# Sheet3.net
KiCad netlist of a schematic drawn in Altium Designer
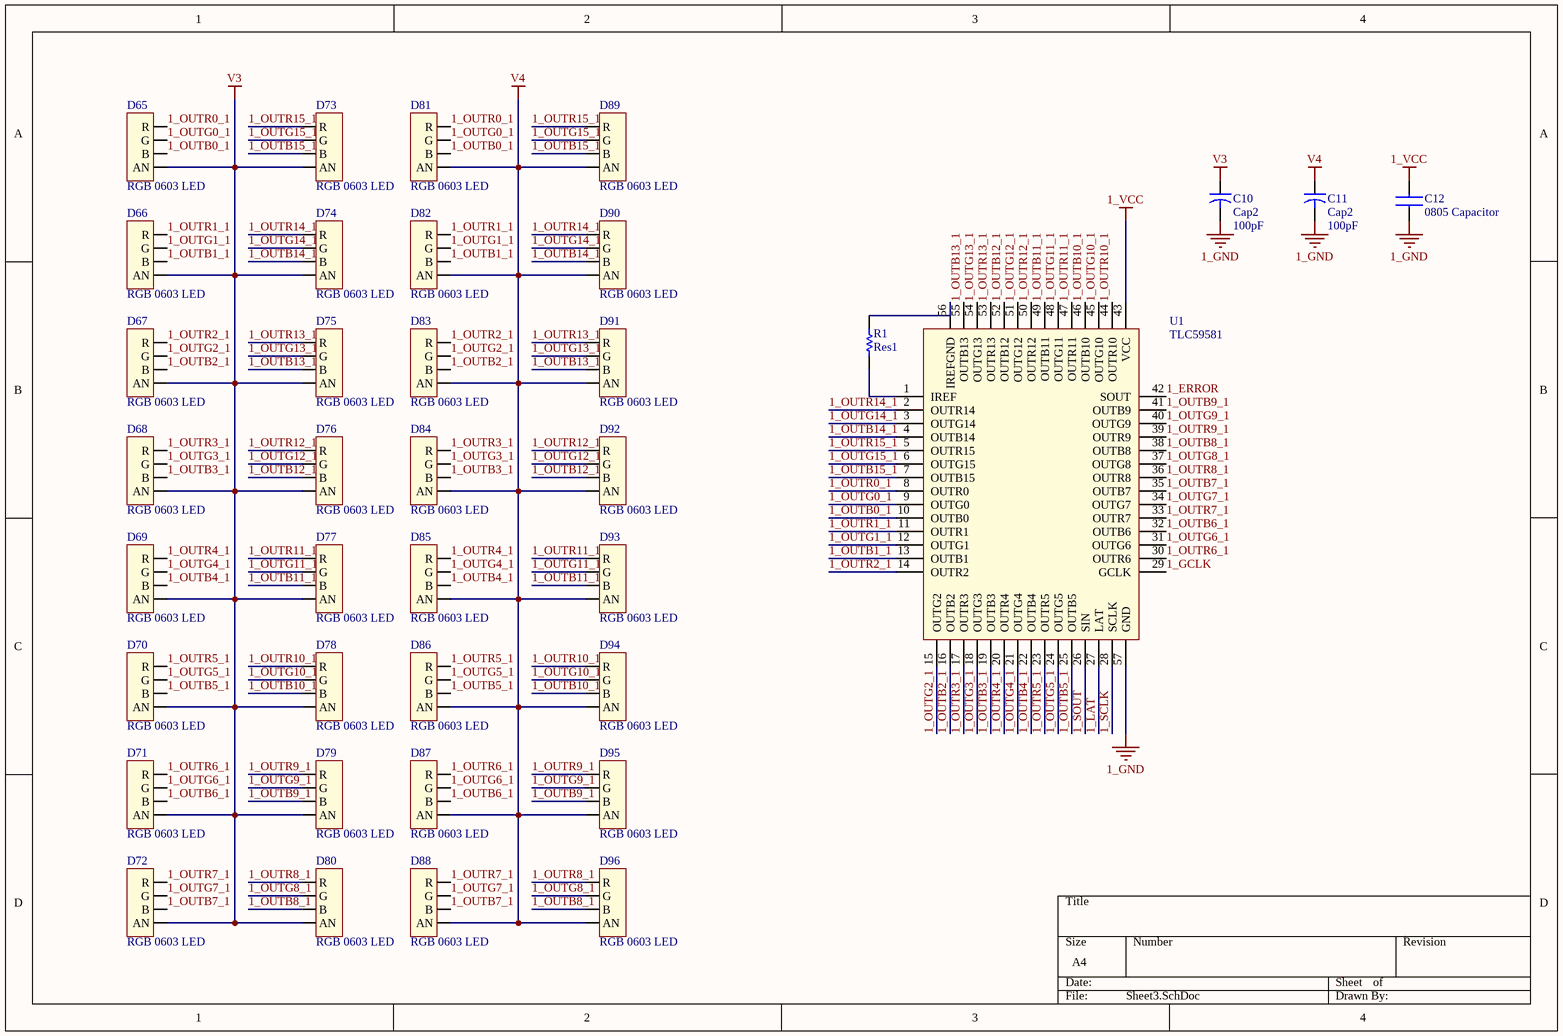
[diagram p0: Sheet3.SchDoc]

(export (version "E")
  (design (tool "Eeschema 10.0.6"))
  (components
    (comp (ref "C10")
      (value "Cap2")
      (footprint "CAPR5-4X5")
      (description "Capacitor")
      (fields (field (name "ALTIUM_VALUE") "100pF") (field (name "PUBLISHER") "Altium Limited"))
      (libsource (lib "Miscellaneous Devices") (part "Cap2"))
    )
    (comp (ref "C11")
      (value "Cap2")
      (footprint "CAPR5-4X5")
      (description "Capacitor")
      (fields (field (name "ALTIUM_VALUE") "100pF") (field (name "PUBLISHER") "Altium Limited"))
      (libsource (lib "Miscellaneous Devices") (part "Cap2"))
    )
    (comp (ref "C12")
      (value "0805 Capacitor")
      (footprint "0805 Capacitor")
      (libsource (lib "Schlib1") (part "0805 Capacitor"))
    )
    (comp (ref "D65")
      (value "RGB 0603 LED")
      (footprint "RGB LED")
      (libsource (lib "") (part "RGB 0603 LED_1"))
    )
    (comp (ref "D66")
      (value "RGB 0603 LED")
      (footprint "RGB LED")
      (libsource (lib "") (part "RGB 0603 LED_1"))
    )
    (comp (ref "D67")
      (value "RGB 0603 LED")
      (footprint "RGB LED")
      (libsource (lib "") (part "RGB 0603 LED_1"))
    )
    (comp (ref "D68")
      (value "RGB 0603 LED")
      (footprint "RGB LED")
      (libsource (lib "") (part "RGB 0603 LED_1"))
    )
    (comp (ref "D69")
      (value "RGB 0603 LED")
      (footprint "RGB LED")
      (libsource (lib "") (part "RGB 0603 LED_1"))
    )
    (comp (ref "D70")
      (value "RGB 0603 LED")
      (footprint "RGB LED")
      (libsource (lib "") (part "RGB 0603 LED_1"))
    )
    (comp (ref "D71")
      (value "RGB 0603 LED")
      (footprint "RGB LED")
      (libsource (lib "") (part "RGB 0603 LED_1"))
    )
    (comp (ref "D72")
      (value "RGB 0603 LED")
      (footprint "RGB LED")
      (libsource (lib "") (part "RGB 0603 LED_1"))
    )
    (comp (ref "D73")
      (value "RGB 0603 LED")
      (footprint "RGB LED")
      (libsource (lib "Schlib1") (part "RGB 0603 LED"))
    )
    (comp (ref "D74")
      (value "RGB 0603 LED")
      (footprint "RGB LED")
      (libsource (lib "Schlib1") (part "RGB 0603 LED"))
    )
    (comp (ref "D75")
      (value "RGB 0603 LED")
      (footprint "RGB LED")
      (libsource (lib "Schlib1") (part "RGB 0603 LED"))
    )
    (comp (ref "D76")
      (value "RGB 0603 LED")
      (footprint "RGB LED")
      (libsource (lib "Schlib1") (part "RGB 0603 LED"))
    )
    (comp (ref "D77")
      (value "RGB 0603 LED")
      (footprint "RGB LED")
      (libsource (lib "Schlib1") (part "RGB 0603 LED"))
    )
    (comp (ref "D78")
      (value "RGB 0603 LED")
      (footprint "RGB LED")
      (libsource (lib "Schlib1") (part "RGB 0603 LED"))
    )
    (comp (ref "D79")
      (value "RGB 0603 LED")
      (footprint "RGB LED")
      (libsource (lib "Schlib1") (part "RGB 0603 LED"))
    )
    (comp (ref "D80")
      (value "RGB 0603 LED")
      (footprint "RGB LED")
      (libsource (lib "Schlib1") (part "RGB 0603 LED"))
    )
    (comp (ref "D81")
      (value "RGB 0603 LED")
      (footprint "RGB LED")
      (libsource (lib "") (part "RGB 0603 LED_1"))
    )
    (comp (ref "D82")
      (value "RGB 0603 LED")
      (footprint "RGB LED")
      (libsource (lib "") (part "RGB 0603 LED_1"))
    )
    (comp (ref "D83")
      (value "RGB 0603 LED")
      (footprint "RGB LED")
      (libsource (lib "") (part "RGB 0603 LED_1"))
    )
    (comp (ref "D84")
      (value "RGB 0603 LED")
      (footprint "RGB LED")
      (libsource (lib "") (part "RGB 0603 LED_1"))
    )
    (comp (ref "D85")
      (value "RGB 0603 LED")
      (footprint "RGB LED")
      (libsource (lib "") (part "RGB 0603 LED_1"))
    )
    (comp (ref "D86")
      (value "RGB 0603 LED")
      (footprint "RGB LED")
      (libsource (lib "") (part "RGB 0603 LED_1"))
    )
    (comp (ref "D87")
      (value "RGB 0603 LED")
      (footprint "RGB LED")
      (libsource (lib "") (part "RGB 0603 LED_1"))
    )
    (comp (ref "D88")
      (value "RGB 0603 LED")
      (footprint "RGB LED")
      (libsource (lib "") (part "RGB 0603 LED_1"))
    )
    (comp (ref "D89")
      (value "RGB 0603 LED")
      (footprint "RGB LED")
      (libsource (lib "Schlib1") (part "RGB 0603 LED"))
    )
    (comp (ref "D90")
      (value "RGB 0603 LED")
      (footprint "RGB LED")
      (libsource (lib "Schlib1") (part "RGB 0603 LED"))
    )
    (comp (ref "D91")
      (value "RGB 0603 LED")
      (footprint "RGB LED")
      (libsource (lib "Schlib1") (part "RGB 0603 LED"))
    )
    (comp (ref "D92")
      (value "RGB 0603 LED")
      (footprint "RGB LED")
      (libsource (lib "Schlib1") (part "RGB 0603 LED"))
    )
    (comp (ref "D93")
      (value "RGB 0603 LED")
      (footprint "RGB LED")
      (libsource (lib "Schlib1") (part "RGB 0603 LED"))
    )
    (comp (ref "D94")
      (value "RGB 0603 LED")
      (footprint "RGB LED")
      (libsource (lib "Schlib1") (part "RGB 0603 LED"))
    )
    (comp (ref "D95")
      (value "RGB 0603 LED")
      (footprint "RGB LED")
      (libsource (lib "Schlib1") (part "RGB 0603 LED"))
    )
    (comp (ref "D96")
      (value "RGB 0603 LED")
      (footprint "RGB LED")
      (libsource (lib "Schlib1") (part "RGB 0603 LED"))
    )
    (comp (ref "R1")
      (value "Res1")
      (footprint "AXIAL-0.3")
      (description "Resistor")
      (fields (field (name "PUBLISHER") "Altium Limited"))
      (libsource (lib "Miscellaneous Devices") (part "Res1"))
    )
    (comp (ref "U1") (value "TLC59581") (footprint "TLC59581") (libsource (lib "Schlib1") (part "TLC59581")))
  )
  (nets
    (net (code "1") (name "/1_ERROR") (class "Default")
      (node (ref "U1") (pin "42") (pinfunction "SOUT_42") (pintype "passive"))
    )
    (net (code "2") (name "/1_GCLK") (class "Default")
      (node (ref "U1") (pin "29") (pinfunction "GCLK_29") (pintype "passive"))
    )
    (net (code "3") (name "/1_LAT") (class "Default")
      (node (ref "U1") (pin "27") (pinfunction "LAT_27") (pintype "passive"))
    )
    (net (code "4") (name "/1_OUTB0_1") (class "Default")
      (node (ref "D65") (pin "3") (pinfunction "B_3") (pintype "passive"))
      (node (ref "D81") (pin "3") (pinfunction "B_3") (pintype "passive"))
      (node (ref "U1") (pin "10") (pinfunction "OUTB0_10") (pintype "passive"))
    )
    (net (code "5") (name "/1_OUTB1_1") (class "Default")
      (node (ref "D66") (pin "3") (pinfunction "B_3") (pintype "passive"))
      (node (ref "D82") (pin "3") (pinfunction "B_3") (pintype "passive"))
      (node (ref "U1") (pin "13") (pinfunction "OUTB1_13") (pintype "passive"))
    )
    (net (code "6") (name "/1_OUTB2_1") (class "Default")
      (node (ref "D67") (pin "3") (pinfunction "B_3") (pintype "passive"))
      (node (ref "D83") (pin "3") (pinfunction "B_3") (pintype "passive"))
      (node (ref "U1") (pin "16") (pinfunction "OUTB2_16") (pintype "passive"))
    )
    (net (code "7") (name "/1_OUTB3_1") (class "Default")
      (node (ref "D68") (pin "3") (pinfunction "B_3") (pintype "passive"))
      (node (ref "D84") (pin "3") (pinfunction "B_3") (pintype "passive"))
      (node (ref "U1") (pin "19") (pinfunction "OUTB3_19") (pintype "passive"))
    )
    (net (code "8") (name "/1_OUTB4_1") (class "Default")
      (node (ref "D69") (pin "3") (pinfunction "B_3") (pintype "passive"))
      (node (ref "D85") (pin "3") (pinfunction "B_3") (pintype "passive"))
      (node (ref "U1") (pin "22") (pinfunction "OUTB4_22") (pintype "passive"))
    )
    (net (code "9") (name "/1_OUTB5_1") (class "Default")
      (node (ref "D70") (pin "3") (pinfunction "B_3") (pintype "passive"))
      (node (ref "D86") (pin "3") (pinfunction "B_3") (pintype "passive"))
      (node (ref "U1") (pin "25") (pinfunction "OUTB5_25") (pintype "passive"))
    )
    (net (code "10") (name "/1_OUTB6_1") (class "Default")
      (node (ref "D71") (pin "3") (pinfunction "B_3") (pintype "passive"))
      (node (ref "D87") (pin "3") (pinfunction "B_3") (pintype "passive"))
      (node (ref "U1") (pin "32") (pinfunction "OUTB6_32") (pintype "passive"))
    )
    (net (code "11") (name "/1_OUTB7_1") (class "Default")
      (node (ref "D72") (pin "3") (pinfunction "B_3") (pintype "passive"))
      (node (ref "D88") (pin "3") (pinfunction "B_3") (pintype "passive"))
      (node (ref "U1") (pin "35") (pinfunction "OUTB7_35") (pintype "passive"))
    )
    (net (code "12") (name "/1_OUTB8_1") (class "Default")
      (node (ref "D80") (pin "3") (pinfunction "B_3") (pintype "passive"))
      (node (ref "D96") (pin "3") (pinfunction "B_3") (pintype "passive"))
      (node (ref "U1") (pin "38") (pinfunction "OUTB8_38") (pintype "passive"))
    )
    (net (code "13") (name "/1_OUTB9_1") (class "Default")
      (node (ref "D79") (pin "3") (pinfunction "B_3") (pintype "passive"))
      (node (ref "D95") (pin "3") (pinfunction "B_3") (pintype "passive"))
      (node (ref "U1") (pin "41") (pinfunction "OUTB9_41") (pintype "passive"))
    )
    (net (code "14") (name "/1_OUTB10_1") (class "Default")
      (node (ref "D78") (pin "3") (pinfunction "B_3") (pintype "passive"))
      (node (ref "D94") (pin "3") (pinfunction "B_3") (pintype "passive"))
      (node (ref "U1") (pin "46") (pinfunction "OUTB10_46") (pintype "passive"))
    )
    (net (code "15") (name "/1_OUTB11_1") (class "Default")
      (node (ref "D77") (pin "3") (pinfunction "B_3") (pintype "passive"))
      (node (ref "D93") (pin "3") (pinfunction "B_3") (pintype "passive"))
      (node (ref "U1") (pin "49") (pinfunction "OUTB11_49") (pintype "passive"))
    )
    (net (code "16") (name "/1_OUTB12_1") (class "Default")
      (node (ref "D76") (pin "3") (pinfunction "B_3") (pintype "passive"))
      (node (ref "D92") (pin "3") (pinfunction "B_3") (pintype "passive"))
      (node (ref "U1") (pin "52") (pinfunction "OUTB12_52") (pintype "passive"))
    )
    (net (code "17") (name "/1_OUTB13_1") (class "Default")
      (node (ref "D75") (pin "3") (pinfunction "B_3") (pintype "passive"))
      (node (ref "D91") (pin "3") (pinfunction "B_3") (pintype "passive"))
      (node (ref "U1") (pin "55") (pinfunction "OUTB13_55") (pintype "passive"))
    )
    (net (code "18") (name "/1_OUTB14_1") (class "Default")
      (node (ref "D74") (pin "3") (pinfunction "B_3") (pintype "passive"))
      (node (ref "D90") (pin "3") (pinfunction "B_3") (pintype "passive"))
      (node (ref "U1") (pin "4") (pinfunction "OUTB14_4") (pintype "passive"))
    )
    (net (code "19") (name "/1_OUTB15_1") (class "Default")
      (node (ref "D73") (pin "3") (pinfunction "B_3") (pintype "passive"))
      (node (ref "D89") (pin "3") (pinfunction "B_3") (pintype "passive"))
      (node (ref "U1") (pin "7") (pinfunction "OUTB15_7") (pintype "passive"))
    )
    (net (code "20") (name "/1_OUTG0_1") (class "Default")
      (node (ref "D65") (pin "2") (pinfunction "G_2") (pintype "passive"))
      (node (ref "D81") (pin "2") (pinfunction "G_2") (pintype "passive"))
      (node (ref "U1") (pin "9") (pinfunction "OUTG0_9") (pintype "passive"))
    )
    (net (code "21") (name "/1_OUTG1_1") (class "Default")
      (node (ref "D66") (pin "2") (pinfunction "G_2") (pintype "passive"))
      (node (ref "D82") (pin "2") (pinfunction "G_2") (pintype "passive"))
      (node (ref "U1") (pin "12") (pinfunction "OUTG1_12") (pintype "passive"))
    )
    (net (code "22") (name "/1_OUTG2_1") (class "Default")
      (node (ref "D67") (pin "2") (pinfunction "G_2") (pintype "passive"))
      (node (ref "D83") (pin "2") (pinfunction "G_2") (pintype "passive"))
      (node (ref "U1") (pin "15") (pinfunction "OUTG2_15") (pintype "passive"))
    )
    (net (code "23") (name "/1_OUTG3_1") (class "Default")
      (node (ref "D68") (pin "2") (pinfunction "G_2") (pintype "passive"))
      (node (ref "D84") (pin "2") (pinfunction "G_2") (pintype "passive"))
      (node (ref "U1") (pin "18") (pinfunction "OUTG3_18") (pintype "passive"))
    )
    (net (code "24") (name "/1_OUTG4_1") (class "Default")
      (node (ref "D69") (pin "2") (pinfunction "G_2") (pintype "passive"))
      (node (ref "D85") (pin "2") (pinfunction "G_2") (pintype "passive"))
      (node (ref "U1") (pin "21") (pinfunction "OUTG4_21") (pintype "passive"))
    )
    (net (code "25") (name "/1_OUTG5_1") (class "Default")
      (node (ref "D70") (pin "2") (pinfunction "G_2") (pintype "passive"))
      (node (ref "D86") (pin "2") (pinfunction "G_2") (pintype "passive"))
      (node (ref "U1") (pin "24") (pinfunction "OUTG5_24") (pintype "passive"))
    )
    (net (code "26") (name "/1_OUTG6_1") (class "Default")
      (node (ref "D71") (pin "2") (pinfunction "G_2") (pintype "passive"))
      (node (ref "D87") (pin "2") (pinfunction "G_2") (pintype "passive"))
      (node (ref "U1") (pin "31") (pinfunction "OUTG6_31") (pintype "passive"))
    )
    (net (code "27") (name "/1_OUTG7_1") (class "Default")
      (node (ref "D72") (pin "2") (pinfunction "G_2") (pintype "passive"))
      (node (ref "D88") (pin "2") (pinfunction "G_2") (pintype "passive"))
      (node (ref "U1") (pin "34") (pinfunction "OUTG7_34") (pintype "passive"))
    )
    (net (code "28") (name "/1_OUTG8_1") (class "Default")
      (node (ref "D80") (pin "2") (pinfunction "G_2") (pintype "passive"))
      (node (ref "D96") (pin "2") (pinfunction "G_2") (pintype "passive"))
      (node (ref "U1") (pin "37") (pinfunction "OUTG8_37") (pintype "passive"))
    )
    (net (code "29") (name "/1_OUTG9_1") (class "Default")
      (node (ref "D79") (pin "2") (pinfunction "G_2") (pintype "passive"))
      (node (ref "D95") (pin "2") (pinfunction "G_2") (pintype "passive"))
      (node (ref "U1") (pin "40") (pinfunction "OUTG9_40") (pintype "passive"))
    )
    (net (code "30") (name "/1_OUTG10_1") (class "Default")
      (node (ref "D78") (pin "2") (pinfunction "G_2") (pintype "passive"))
      (node (ref "D94") (pin "2") (pinfunction "G_2") (pintype "passive"))
      (node (ref "U1") (pin "45") (pinfunction "OUTG10_45") (pintype "passive"))
    )
    (net (code "31") (name "/1_OUTG11_1") (class "Default")
      (node (ref "D77") (pin "2") (pinfunction "G_2") (pintype "passive"))
      (node (ref "D93") (pin "2") (pinfunction "G_2") (pintype "passive"))
      (node (ref "U1") (pin "48") (pinfunction "OUTG11_48") (pintype "passive"))
    )
    (net (code "32") (name "/1_OUTG12_1") (class "Default")
      (node (ref "D76") (pin "2") (pinfunction "G_2") (pintype "passive"))
      (node (ref "D92") (pin "2") (pinfunction "G_2") (pintype "passive"))
      (node (ref "U1") (pin "51") (pinfunction "OUTG12_51") (pintype "passive"))
    )
    (net (code "33") (name "/1_OUTG13_1") (class "Default")
      (node (ref "D75") (pin "2") (pinfunction "G_2") (pintype "passive"))
      (node (ref "D91") (pin "2") (pinfunction "G_2") (pintype "passive"))
      (node (ref "U1") (pin "54") (pinfunction "OUTG13_54") (pintype "passive"))
    )
    (net (code "34") (name "/1_OUTG14_1") (class "Default")
      (node (ref "D74") (pin "2") (pinfunction "G_2") (pintype "passive"))
      (node (ref "D90") (pin "2") (pinfunction "G_2") (pintype "passive"))
      (node (ref "U1") (pin "3") (pinfunction "OUTG14_3") (pintype "passive"))
    )
    (net (code "35") (name "/1_OUTG15_1") (class "Default")
      (node (ref "D73") (pin "2") (pinfunction "G_2") (pintype "passive"))
      (node (ref "D89") (pin "2") (pinfunction "G_2") (pintype "passive"))
      (node (ref "U1") (pin "6") (pinfunction "OUTG15_6") (pintype "passive"))
    )
    (net (code "36") (name "/1_OUTR0_1") (class "Default")
      (node (ref "D65") (pin "1") (pinfunction "R_1") (pintype "passive"))
      (node (ref "D81") (pin "1") (pinfunction "R_1") (pintype "passive"))
      (node (ref "U1") (pin "8") (pinfunction "OUTR0_8") (pintype "passive"))
    )
    (net (code "37") (name "/1_OUTR1_1") (class "Default")
      (node (ref "D66") (pin "1") (pinfunction "R_1") (pintype "passive"))
      (node (ref "D82") (pin "1") (pinfunction "R_1") (pintype "passive"))
      (node (ref "U1") (pin "11") (pinfunction "OUTR1_11") (pintype "passive"))
    )
    (net (code "38") (name "/1_OUTR2_1") (class "Default")
      (node (ref "D67") (pin "1") (pinfunction "R_1") (pintype "passive"))
      (node (ref "D83") (pin "1") (pinfunction "R_1") (pintype "passive"))
      (node (ref "U1") (pin "14") (pinfunction "OUTR2_14") (pintype "passive"))
    )
    (net (code "39") (name "/1_OUTR3_1") (class "Default")
      (node (ref "D68") (pin "1") (pinfunction "R_1") (pintype "passive"))
      (node (ref "D84") (pin "1") (pinfunction "R_1") (pintype "passive"))
      (node (ref "U1") (pin "17") (pinfunction "OUTR3_17") (pintype "passive"))
    )
    (net (code "40") (name "/1_OUTR4_1") (class "Default")
      (node (ref "D69") (pin "1") (pinfunction "R_1") (pintype "passive"))
      (node (ref "D85") (pin "1") (pinfunction "R_1") (pintype "passive"))
      (node (ref "U1") (pin "20") (pinfunction "OUTR4_20") (pintype "passive"))
    )
    (net (code "41") (name "/1_OUTR5_1") (class "Default")
      (node (ref "D70") (pin "1") (pinfunction "R_1") (pintype "passive"))
      (node (ref "D86") (pin "1") (pinfunction "R_1") (pintype "passive"))
      (node (ref "U1") (pin "23") (pinfunction "OUTR5_23") (pintype "passive"))
    )
    (net (code "42") (name "/1_OUTR6_1") (class "Default")
      (node (ref "D71") (pin "1") (pinfunction "R_1") (pintype "passive"))
      (node (ref "D87") (pin "1") (pinfunction "R_1") (pintype "passive"))
      (node (ref "U1") (pin "30") (pinfunction "OUTR6_30") (pintype "passive"))
    )
    (net (code "43") (name "/1_OUTR7_1") (class "Default")
      (node (ref "D72") (pin "1") (pinfunction "R_1") (pintype "passive"))
      (node (ref "D88") (pin "1") (pinfunction "R_1") (pintype "passive"))
      (node (ref "U1") (pin "33") (pinfunction "OUTR7_33") (pintype "passive"))
    )
    (net (code "44") (name "/1_OUTR8_1") (class "Default")
      (node (ref "D80") (pin "1") (pinfunction "R_1") (pintype "passive"))
      (node (ref "D96") (pin "1") (pinfunction "R_1") (pintype "passive"))
      (node (ref "U1") (pin "36") (pinfunction "OUTR8_36") (pintype "passive"))
    )
    (net (code "45") (name "/1_OUTR9_1") (class "Default")
      (node (ref "D79") (pin "1") (pinfunction "R_1") (pintype "passive"))
      (node (ref "D95") (pin "1") (pinfunction "R_1") (pintype "passive"))
      (node (ref "U1") (pin "39") (pinfunction "OUTR9_39") (pintype "passive"))
    )
    (net (code "46") (name "/1_OUTR10_1") (class "Default")
      (node (ref "D78") (pin "1") (pinfunction "R_1") (pintype "passive"))
      (node (ref "D94") (pin "1") (pinfunction "R_1") (pintype "passive"))
      (node (ref "U1") (pin "44") (pinfunction "OUTR10_44") (pintype "passive"))
    )
    (net (code "47") (name "/1_OUTR11_1") (class "Default")
      (node (ref "D77") (pin "1") (pinfunction "R_1") (pintype "passive"))
      (node (ref "D93") (pin "1") (pinfunction "R_1") (pintype "passive"))
      (node (ref "U1") (pin "47") (pinfunction "OUTR11_47") (pintype "passive"))
    )
    (net (code "48") (name "/1_OUTR12_1") (class "Default")
      (node (ref "D76") (pin "1") (pinfunction "R_1") (pintype "passive"))
      (node (ref "D92") (pin "1") (pinfunction "R_1") (pintype "passive"))
      (node (ref "U1") (pin "50") (pinfunction "OUTR12_50") (pintype "passive"))
    )
    (net (code "49") (name "/1_OUTR13_1") (class "Default")
      (node (ref "D75") (pin "1") (pinfunction "R_1") (pintype "passive"))
      (node (ref "D91") (pin "1") (pinfunction "R_1") (pintype "passive"))
      (node (ref "U1") (pin "53") (pinfunction "OUTR13_53") (pintype "passive"))
    )
    (net (code "50") (name "/1_OUTR14_1") (class "Default")
      (node (ref "D74") (pin "1") (pinfunction "R_1") (pintype "passive"))
      (node (ref "D90") (pin "1") (pinfunction "R_1") (pintype "passive"))
      (node (ref "U1") (pin "2") (pinfunction "OUTR14_2") (pintype "passive"))
    )
    (net (code "51") (name "/1_OUTR15_1") (class "Default")
      (node (ref "D73") (pin "1") (pinfunction "R_1") (pintype "passive"))
      (node (ref "D89") (pin "1") (pinfunction "R_1") (pintype "passive"))
      (node (ref "U1") (pin "5") (pinfunction "OUTR15_5") (pintype "passive"))
    )
    (net (code "52") (name "/1_SCLK") (class "Default")
      (node (ref "U1") (pin "28") (pinfunction "SCLK_28") (pintype "passive"))
    )
    (net (code "53") (name "/1_SOUT") (class "Default")
      (node (ref "U1") (pin "26") (pinfunction "SIN_26") (pintype "passive"))
    )
    (net (code "54") (name "1_GND") (class "Default")
      (node (ref "C10") (pin "2") (pinfunction "2_2") (pintype "passive"))
      (node (ref "C11") (pin "2") (pinfunction "2_2") (pintype "passive"))
      (node (ref "C12") (pin "1") (pinfunction "1_1") (pintype "passive"))
      (node (ref "U1") (pin "57") (pinfunction "GND_57") (pintype "passive"))
    )
    (net (code "55") (name "1_VCC") (class "Default")
      (node (ref "C12") (pin "2") (pinfunction "2_2") (pintype "passive"))
      (node (ref "U1") (pin "43") (pinfunction "VCC_43") (pintype "passive"))
    )
    (net (code "56") (name "Net-(U1-IREF)") (class "Default")
      (node (ref "R1") (pin "1") (pinfunction "1_1") (pintype "passive"))
      (node (ref "U1") (pin "1") (pinfunction "IREF_1") (pintype "passive"))
    )
    (net (code "57") (name "Net-(U1-IREFGND)") (class "Default")
      (node (ref "R1") (pin "2") (pinfunction "2_2") (pintype "passive"))
      (node (ref "U1") (pin "56") (pinfunction "IREFGND_56") (pintype "passive"))
    )
    (net (code "58") (name "V3") (class "Default")
      (node (ref "C10") (pin "1") (pinfunction "1_1") (pintype "passive"))
      (node (ref "D65") (pin "4") (pinfunction "AN_4") (pintype "passive"))
      (node (ref "D66") (pin "4") (pinfunction "AN_4") (pintype "passive"))
      (node (ref "D67") (pin "4") (pinfunction "AN_4") (pintype "passive"))
      (node (ref "D68") (pin "4") (pinfunction "AN_4") (pintype "passive"))
      (node (ref "D69") (pin "4") (pinfunction "AN_4") (pintype "passive"))
      (node (ref "D70") (pin "4") (pinfunction "AN_4") (pintype "passive"))
      (node (ref "D71") (pin "4") (pinfunction "AN_4") (pintype "passive"))
      (node (ref "D72") (pin "4") (pinfunction "AN_4") (pintype "passive"))
      (node (ref "D73") (pin "4") (pinfunction "AN_4") (pintype "passive"))
      (node (ref "D74") (pin "4") (pinfunction "AN_4") (pintype "passive"))
      (node (ref "D75") (pin "4") (pinfunction "AN_4") (pintype "passive"))
      (node (ref "D76") (pin "4") (pinfunction "AN_4") (pintype "passive"))
      (node (ref "D77") (pin "4") (pinfunction "AN_4") (pintype "passive"))
      (node (ref "D78") (pin "4") (pinfunction "AN_4") (pintype "passive"))
      (node (ref "D79") (pin "4") (pinfunction "AN_4") (pintype "passive"))
      (node (ref "D80") (pin "4") (pinfunction "AN_4") (pintype "passive"))
    )
    (net (code "59") (name "V4") (class "Default")
      (node (ref "C11") (pin "1") (pinfunction "1_1") (pintype "passive"))
      (node (ref "D81") (pin "4") (pinfunction "AN_4") (pintype "passive"))
      (node (ref "D82") (pin "4") (pinfunction "AN_4") (pintype "passive"))
      (node (ref "D83") (pin "4") (pinfunction "AN_4") (pintype "passive"))
      (node (ref "D84") (pin "4") (pinfunction "AN_4") (pintype "passive"))
      (node (ref "D85") (pin "4") (pinfunction "AN_4") (pintype "passive"))
      (node (ref "D86") (pin "4") (pinfunction "AN_4") (pintype "passive"))
      (node (ref "D87") (pin "4") (pinfunction "AN_4") (pintype "passive"))
      (node (ref "D88") (pin "4") (pinfunction "AN_4") (pintype "passive"))
      (node (ref "D89") (pin "4") (pinfunction "AN_4") (pintype "passive"))
      (node (ref "D90") (pin "4") (pinfunction "AN_4") (pintype "passive"))
      (node (ref "D91") (pin "4") (pinfunction "AN_4") (pintype "passive"))
      (node (ref "D92") (pin "4") (pinfunction "AN_4") (pintype "passive"))
      (node (ref "D93") (pin "4") (pinfunction "AN_4") (pintype "passive"))
      (node (ref "D94") (pin "4") (pinfunction "AN_4") (pintype "passive"))
      (node (ref "D95") (pin "4") (pinfunction "AN_4") (pintype "passive"))
      (node (ref "D96") (pin "4") (pinfunction "AN_4") (pintype "passive"))
    )
  )
)
